# ezfet.net
KiCad netlist of a schematic drawn in Altium Designer
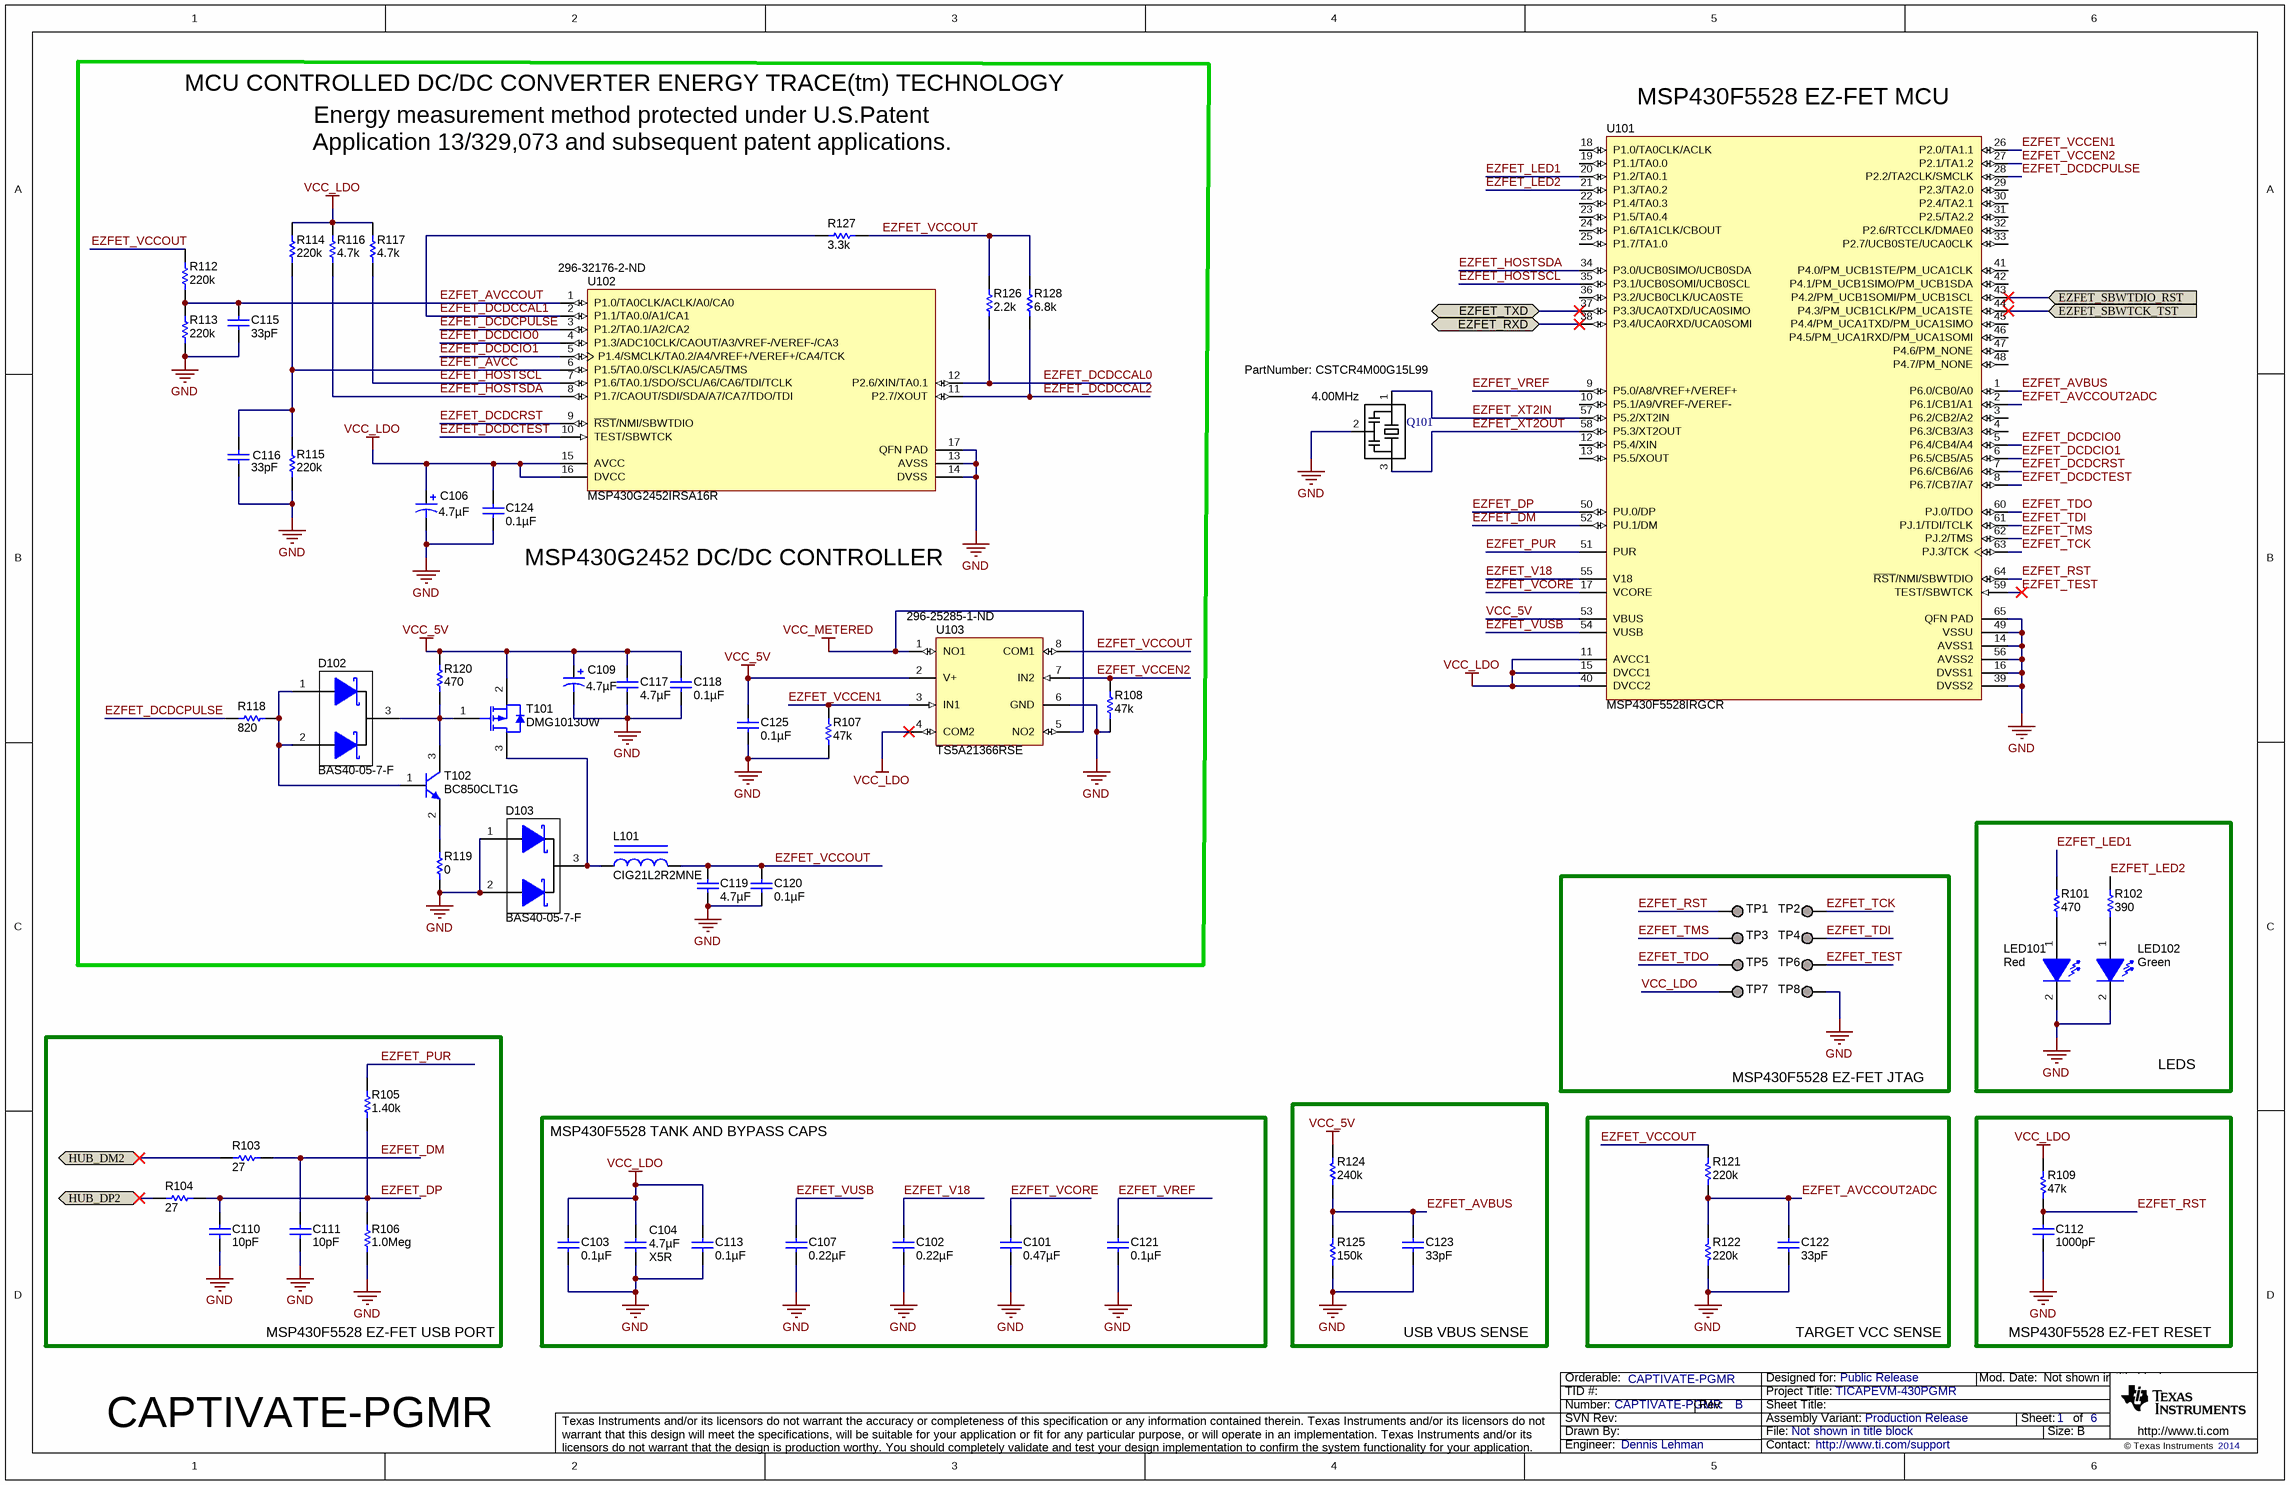
[diagram p0: ezfet.SchDoc]

(export (version "E")
  (design (tool "Eeschema 10.0.6"))
  (components
    (comp (ref "C101")
      (value "GRM155R61A474KE15D")
      (footprint "0402")
      (description "CAP, CERM, 0.47uF, 10V, +/-10%, X5R, 0402")
      (fields
        (field (name "VALUEDISPLAYED") "0.47µF")
        (field (name "MANUFACTURER") "MuRata")
        (field (name "PUBLISHER") "Texas Instruments")
      )
      (libsource (lib "Capacitor_Ceramic") (part "GRM155R61A474KE15D"))
    )
    (comp (ref "C102")
      (value "GRM155R61A224KE19D")
      (footprint "0402")
      (description "CAP, CERM, 0.22uF, 10V, +/-10%, X5R, 0402")
      (fields
        (field (name "VALUEDISPLAYED") "0.22µF")
        (field (name "MANUFACTURER") "MuRata")
        (field (name "PUBLISHER") "Texas Instruments")
      )
      (libsource (lib "Capacitor_Ceramic") (part "GRM155R61A224KE19D"))
    )
    (comp (ref "C103")
      (value "C1005X5R1A104K")
      (footprint "0402")
      (description "CAP, CERM, 0.1uF, 10V, +/-10%, X5R, 0402")
      (fields
        (field (name "VALUEDISPLAYED") "0.1µF")
        (field (name "MANUFACTURER") "TDK")
        (field (name "PUBLISHER") "Texas Instruments")
      )
      (libsource (lib "Capacitor_Ceramic") (part "C1005X5R1A104K"))
    )
    (comp (ref "C104")
      (value "CGB3B1X5R1A475K055AC")
      (footprint "0603")
      (description "CAP, CERM, 4.7 µF, 10 V, +/- 10%, X5R, 0603")
      (fields
        (field (name "VALUEDISPLAYED") "4.7µF")
        (field (name "MANUFACTURER") "TDK")
        (field (name "TEMPCO") "X5R")
        (field (name "PUBLISHER") "Texas Instruments")
      )
      (libsource (lib "Capacitor_Ceramic") (part "CGB3B1X5R1A475K055AC"))
    )
    (comp (ref "C106")
      (value "293D475X9010A2TE3")
      (footprint "3216-18")
      (description "CAP, TA, 4.7 µF, 10 V, +/- 10%, 5 ohm, SMD")
      (fields
        (field (name "VALUEDISPLAYED") "4.7µF")
        (field (name "MANUFACTURER") "Vishay-Sprague")
        (field (name "PUBLISHER") "Texas Instruments")
      )
      (libsource (lib "Capacitor_Tantalum") (part "293D475X9010A2TE3"))
    )
    (comp (ref "C107")
      (value "GRM155R61A224KE19D")
      (footprint "0402")
      (description "CAP, CERM, 0.22uF, 10V, +/-10%, X5R, 0402")
      (fields
        (field (name "VALUEDISPLAYED") "0.22µF")
        (field (name "MANUFACTURER") "MuRata")
        (field (name "PUBLISHER") "Texas Instruments")
      )
      (libsource (lib "Capacitor_Ceramic") (part "GRM155R61A224KE19D"))
    )
    (comp (ref "C109")
      (value "293D475X9010A2TE3")
      (footprint "3216-18")
      (description "CAP, TA, 4.7 µF, 10 V, +/- 10%, 5 ohm, SMD")
      (fields
        (field (name "VALUEDISPLAYED") "4.7µF")
        (field (name "MANUFACTURER") "Vishay-Sprague")
        (field (name "PUBLISHER") "Texas Instruments")
      )
      (libsource (lib "Capacitor_Tantalum") (part "293D475X9010A2TE3"))
    )
    (comp (ref "C110")
      (value "500R07S100JV4T")
      (footprint "0402")
      (description "CAP, CERM, 10pF, 50V, +/-5%, C0G/NP0, 0402")
      (fields
        (field (name "VALUEDISPLAYED") "10pF")
        (field (name "MANUFACTURER") "Johanson Technology")
        (field (name "PUBLISHER") "Texas Instruments")
      )
      (libsource (lib "Capacitor_Ceramic") (part "500R07S100JV4T"))
    )
    (comp (ref "C111")
      (value "500R07S100JV4T")
      (footprint "0402")
      (description "CAP, CERM, 10pF, 50V, +/-5%, C0G/NP0, 0402")
      (fields
        (field (name "VALUEDISPLAYED") "10pF")
        (field (name "MANUFACTURER") "Johanson Technology")
        (field (name "PUBLISHER") "Texas Instruments")
      )
      (libsource (lib "Capacitor_Ceramic") (part "500R07S100JV4T"))
    )
    (comp (ref "C112")
      (value "C1005X7R1H102K")
      (footprint "0402")
      (description "CAP, CERM, 1000pF, 50V, +/-10%, X7R, 0402")
      (fields
        (field (name "VALUEDISPLAYED") "1000pF")
        (field (name "MANUFACTURER") "TDK")
        (field (name "PUBLISHER") "Texas Instruments")
      )
      (libsource (lib "Capacitor_Ceramic") (part "C1005X7R1H102K"))
    )
    (comp (ref "C113")
      (value "C1005X5R1A104K")
      (footprint "0402")
      (description "CAP, CERM, 0.1uF, 10V, +/-10%, X5R, 0402")
      (fields
        (field (name "VALUEDISPLAYED") "0.1µF")
        (field (name "MANUFACTURER") "TDK")
        (field (name "PUBLISHER") "Texas Instruments")
      )
      (libsource (lib "Capacitor_Ceramic") (part "C1005X5R1A104K"))
    )
    (comp (ref "C115")
      (value "GRM1555C1H330JA01D")
      (footprint "0402")
      (description "CAP, CERM, 33pF, 50V, +/-5%, C0G/NP0, 0402")
      (fields
        (field (name "VALUEDISPLAYED") "33pF")
        (field (name "MANUFACTURER") "MuRata")
        (field (name "PUBLISHER") "Texas Instruments")
      )
      (libsource (lib "Capacitor_Ceramic") (part "GRM1555C1H330JA01D"))
    )
    (comp (ref "C116")
      (value "GRM1555C1H330JA01D")
      (footprint "0402")
      (description "CAP, CERM, 33pF, 50V, +/-5%, C0G/NP0, 0402")
      (fields
        (field (name "VALUEDISPLAYED") "33pF")
        (field (name "MANUFACTURER") "MuRata")
        (field (name "PUBLISHER") "Texas Instruments")
      )
      (libsource (lib "Capacitor_Ceramic") (part "GRM1555C1H330JA01D"))
    )
    (comp (ref "C117")
      (value "0603ZD475KAT2A")
      (footprint "0603")
      (description "CAP, CERM, 4.7 µF, 10 V, +/- 10%, X5R, 0603")
      (fields
        (field (name "VALUEDISPLAYED") "4.7µF")
        (field (name "MANUFACTURER") "AVX")
        (field (name "PUBLISHER") "Texas Instruments")
      )
      (libsource (lib "Capacitor_Ceramic") (part "0603ZD475KAT2A"))
    )
    (comp (ref "C118")
      (value "C1005X5R1A104K")
      (footprint "0402")
      (description "CAP, CERM, 0.1uF, 10V, +/-10%, X5R, 0402")
      (fields
        (field (name "VALUEDISPLAYED") "0.1µF")
        (field (name "MANUFACTURER") "TDK")
        (field (name "PUBLISHER") "Texas Instruments")
      )
      (libsource (lib "Capacitor_Ceramic") (part "C1005X5R1A104K"))
    )
    (comp (ref "C119")
      (value "0603ZD475KAT2A")
      (footprint "0603")
      (description "CAP, CERM, 4.7 µF, 10 V, +/- 10%, X5R, 0603")
      (fields
        (field (name "VALUEDISPLAYED") "4.7µF")
        (field (name "MANUFACTURER") "AVX")
        (field (name "PUBLISHER") "Texas Instruments")
      )
      (libsource (lib "Capacitor_Ceramic") (part "0603ZD475KAT2A"))
    )
    (comp (ref "C120")
      (value "C1005X5R1A104K")
      (footprint "0402")
      (description "CAP, CERM, 0.1uF, 10V, +/-10%, X5R, 0402")
      (fields
        (field (name "VALUEDISPLAYED") "0.1µF")
        (field (name "MANUFACTURER") "TDK")
        (field (name "PUBLISHER") "Texas Instruments")
      )
      (libsource (lib "Capacitor_Ceramic") (part "C1005X5R1A104K"))
    )
    (comp (ref "C121")
      (value "C1005X5R1A104K")
      (footprint "0402")
      (description "CAP, CERM, 0.1uF, 10V, +/-10%, X5R, 0402")
      (fields
        (field (name "VALUEDISPLAYED") "0.1µF")
        (field (name "MANUFACTURER") "TDK")
        (field (name "PUBLISHER") "Texas Instruments")
      )
      (libsource (lib "Capacitor_Ceramic") (part "C1005X5R1A104K"))
    )
    (comp (ref "C122")
      (value "GRM1555C1H330JA01D")
      (footprint "0402")
      (description "CAP, CERM, 33pF, 50V, +/-5%, C0G/NP0, 0402")
      (fields
        (field (name "VALUEDISPLAYED") "33pF")
        (field (name "MANUFACTURER") "MuRata")
        (field (name "PUBLISHER") "Texas Instruments")
      )
      (libsource (lib "Capacitor_Ceramic") (part "GRM1555C1H330JA01D"))
    )
    (comp (ref "C123")
      (value "GRM1555C1H330JA01D")
      (footprint "0402")
      (description "CAP, CERM, 33pF, 50V, +/-5%, C0G/NP0, 0402")
      (fields
        (field (name "VALUEDISPLAYED") "33pF")
        (field (name "MANUFACTURER") "MuRata")
        (field (name "PUBLISHER") "Texas Instruments")
      )
      (libsource (lib "Capacitor_Ceramic") (part "GRM1555C1H330JA01D"))
    )
    (comp (ref "C124")
      (value "C1005X5R1A104K")
      (footprint "0402")
      (description "CAP, CERM, 0.1 µF, 10 V, +/- 10%, X5R, 0402")
      (fields
        (field (name "VALUEDISPLAYED") "0.1µF")
        (field (name "MANUFACTURER") "TDK")
        (field (name "PUBLISHER") "Texas Instruments")
      )
      (libsource (lib "Capacitor_Ceramic") (part "C1005X5R1A104K"))
    )
    (comp (ref "C125")
      (value "C1005X5R1A104K")
      (footprint "0402")
      (description "CAP, CERM, 0.1uF, 10V, +/-10%, X5R, 0402")
      (fields
        (field (name "VALUEDISPLAYED") "0.1µF")
        (field (name "MANUFACTURER") "TDK")
        (field (name "PUBLISHER") "Texas Instruments")
      )
      (libsource (lib "Capacitor_Ceramic") (part "C1005X5R1A104K"))
    )
    (comp (ref "D102")
      (value "BAS40-05-7-F")
      (footprint "SOT-23")
      (description "Diode, Schottky, 40V, 0.2A, SOT-23")
      (fields
        (field (name "MANUFACTURER") "Diodes Inc.")
        (field (name "SYMBOLCREATOR") "a0412235")
        (field (name "PUBLISHER") "Texas Instruments")
      )
      (libsource (lib "Diode") (part "BAS40-05-7-F"))
    )
    (comp (ref "D103")
      (value "BAS40-05-7-F")
      (footprint "SOT-23")
      (description "Diode, Schottky, 40V, 0.2A, SOT-23")
      (fields
        (field (name "MANUFACTURER") "Diodes Inc.")
        (field (name "SYMBOLCREATOR") "a0412235")
        (field (name "PUBLISHER") "Texas Instruments")
      )
      (libsource (lib "Diode") (part "BAS40-05-7-F"))
    )
    (comp (ref "L101")
      (value "CIG21L2R2MNE")
      (footprint "0805_HV")
      (description "Inductor, Shielded, Composite, 2.2uH, 0.95A, 0.16 ohm, SMD")
      (fields (field (name "MANUFACTURER") "Samsung") (field (name "PUBLISHER") "Texas Instruments"))
      (libsource (lib "Inductor_Other") (part "CIG21L2R2MNE"))
    )
    (comp (ref "LED101")
      (value "Red")
      (footprint "LED_LTST-C190_Red")
      (description "LED, Red, SMD")
      (fields
        (field (name "MANUFACTURER") "Lite-On")
        (field (name "PARTNUMBER") "LTST-C190CKT")
        (field (name "PUBLISHER") "Texas Instruments")
      )
      (libsource (lib "LED") (part "LTST-C190CKT"))
    )
    (comp (ref "LED102")
      (value "Green")
      (footprint "LED_LTST-C190")
      (description "LED, Green, SMD")
      (fields
        (field (name "MANUFACTURER") "Lite-On")
        (field (name "PARTNUMBER") "LTST-C190GKT")
        (field (name "PUBLISHER") "Texas Instruments")
      )
      (libsource (lib "LED") (part "LTST-C190GKT"))
    )
    (comp (ref "Q101")
      (value "MURATA-FILTER_CSTCR4M00G15")
      (footprint "CSTCR CERAMIC RESONATOR - MURATA")
      (description "4.00MHz resonator")
      (fields (field (name "VALUE DISPLAYED") "4.00MHz") (field (name "PARTNUMBER") "CSTCR4M00G15L99"))
      (libsource (lib "Captivate Library") (part "MURATA-FILTER_CSTCR4M00G15"))
    )
    (comp (ref "R101")
      (value "470")
      (footprint "0402")
      (description "RES, 470 ohm, 5%, 0.063W, 0402")
      (fields
        (field (name "PARTNUMBER") "CRCW0402470RJNED")
        (field (name "MANUFACTURER") "Vishay-Dale")
        (field (name "PUBLISHER") "Texas Instruments")
      )
      (libsource (lib "Resistor_0402") (part "CRCW0402470RJNED"))
    )
    (comp (ref "R102")
      (value "390")
      (footprint "0402")
      (description "RES, 390 ohm, 5%, 0.063W, 0402")
      (fields
        (field (name "PARTNUMBER") "CRCW0402390RJNED")
        (field (name "MANUFACTURER") "Vishay-Dale")
        (field (name "PUBLISHER") "Texas Instruments")
      )
      (libsource (lib "Resistor_0402") (part "CRCW0402390RJNED"))
    )
    (comp (ref "R103")
      (value "27")
      (footprint "0402")
      (description "RES, 27 ohm, 5%, 0.063W, 0402")
      (fields
        (field (name "PARTNUMBER") "CRCW040227R0JNED")
        (field (name "MANUFACTURER") "Vishay-Dale")
        (field (name "PUBLISHER") "Texas Instruments")
      )
      (libsource (lib "Resistor_0402") (part "CRCW040227R0JNED"))
    )
    (comp (ref "R104")
      (value "27")
      (footprint "0402")
      (description "RES, 27 ohm, 5%, 0.063W, 0402")
      (fields
        (field (name "PARTNUMBER") "CRCW040227R0JNED")
        (field (name "MANUFACTURER") "Vishay-Dale")
        (field (name "PUBLISHER") "Texas Instruments")
      )
      (libsource (lib "Resistor_0402") (part "CRCW040227R0JNED"))
    )
    (comp (ref "R105")
      (value "CRCW04021K40FKED")
      (footprint "0402")
      (description "RES, 1.40 k, 1%, 0.063 W, 0402")
      (fields
        (field (name "MANUFACTURER") "Vishay-Dale")
        (field (name "VALUEDISPLAYED") "1.40k")
        (field (name "PUBLISHER") "Texas Instruments")
      )
      (libsource (lib "Resistor_0402") (part "CRCW04021K40FKED"))
    )
    (comp (ref "R106")
      (value "1.0Meg")
      (footprint "0402")
      (description "RES, 1.0Meg ohm, 5%, 0.063W, 0402")
      (fields
        (field (name "PARTNUMBER") "CRCW04021M00JNED")
        (field (name "MANUFACTURER") "Vishay-Dale")
        (field (name "PUBLISHER") "Texas Instruments")
      )
      (libsource (lib "Resistor_0402") (part "CRCW04021M00JNED"))
    )
    (comp (ref "R107")
      (value "CRCW040247K0JNED")
      (footprint "0402")
      (description "RES, 47 k, 5%, 0.063 W, 0402")
      (fields
        (field (name "MANUFACTURER") "Vishay-Dale")
        (field (name "VALUEDISPLAYED") "47k")
        (field (name "PUBLISHER") "Texas Instruments")
      )
      (libsource (lib "Resistor_0402") (part "CRCW040247K0JNED"))
    )
    (comp (ref "R108")
      (value "CRCW040247K0JNED")
      (footprint "0402")
      (description "RES, 47 k, 5%, 0.063 W, 0402")
      (fields
        (field (name "MANUFACTURER") "Vishay-Dale")
        (field (name "VALUEDISPLAYED") "47k")
        (field (name "PUBLISHER") "Texas Instruments")
      )
      (libsource (lib "Resistor_0402") (part "CRCW040247K0JNED"))
    )
    (comp (ref "R109")
      (value "47k")
      (footprint "0402")
      (description "RES, 47k ohm, 5%, 0.063W, 0402")
      (fields
        (field (name "PARTNUMBER") "CRCW040247K0JNED")
        (field (name "MANUFACTURER") "Vishay-Dale")
        (field (name "PUBLISHER") "Texas Instruments")
      )
      (libsource (lib "Resistor_0402") (part "CRCW040247K0JNED"))
    )
    (comp (ref "R112")
      (value "CRCW0402220KJNED")
      (footprint "0402")
      (description "RES, 220 k, 5%, 0.063 W, 0402")
      (fields
        (field (name "VALUEDISPLAYED") "220k")
        (field (name "MANUFACTURER") "Vishay-Dale")
        (field (name "PUBLISHER") "Texas Instruments")
      )
      (libsource (lib "Resistor_0402") (part "CRCW0402220KJNED"))
    )
    (comp (ref "R113")
      (value "CRCW0402220KJNED")
      (footprint "0402")
      (description "RES, 220 k, 5%, 0.063 W, 0402")
      (fields
        (field (name "VALUEDISPLAYED") "220k")
        (field (name "MANUFACTURER") "Vishay-Dale")
        (field (name "PUBLISHER") "Texas Instruments")
      )
      (libsource (lib "Resistor_0402") (part "CRCW0402220KJNED"))
    )
    (comp (ref "R114")
      (value "CRCW0402220KJNED")
      (footprint "0402")
      (description "RES, 220 k, 5%, 0.063 W, 0402")
      (fields
        (field (name "VALUEDISPLAYED") "220k")
        (field (name "MANUFACTURER") "Vishay-Dale")
        (field (name "PUBLISHER") "Texas Instruments")
      )
      (libsource (lib "Resistor_0402") (part "CRCW0402220KJNED"))
    )
    (comp (ref "R115")
      (value "CRCW0402220KJNED")
      (footprint "0402")
      (description "RES, 220 k, 5%, 0.063 W, 0402")
      (fields
        (field (name "VALUEDISPLAYED") "220k")
        (field (name "MANUFACTURER") "Vishay-Dale")
        (field (name "PUBLISHER") "Texas Instruments")
      )
      (libsource (lib "Resistor_0402") (part "CRCW0402220KJNED"))
    )
    (comp (ref "R116")
      (value "CRCW04024K70JNED")
      (footprint "0402")
      (description "RES, 4.7 k, 5%, 0.063 W, 0402")
      (fields
        (field (name "VALUEDISPLAYED") "4.7k")
        (field (name "MANUFACTURER") "Vishay-Dale")
        (field (name "PUBLISHER") "Texas Instruments")
      )
      (libsource (lib "Resistor_0402") (part "CRCW04024K70JNED"))
    )
    (comp (ref "R117")
      (value "CRCW04024K70JNED")
      (footprint "0402")
      (description "RES, 4.7 k, 5%, 0.063 W, 0402")
      (fields
        (field (name "VALUEDISPLAYED") "4.7k")
        (field (name "MANUFACTURER") "Vishay-Dale")
        (field (name "PUBLISHER") "Texas Instruments")
      )
      (libsource (lib "Resistor_0402") (part "CRCW04024K70JNED"))
    )
    (comp (ref "R118")
      (value "CRCW0402820RJNED")
      (footprint "0402")
      (description "RES, 820, 5%, 0.063 W, 0402")
      (fields
        (field (name "MANUFACTURER") "Vishay-Dale")
        (field (name "VALUEDISPLAYED") "820")
        (field (name "PUBLISHER") "Texas Instruments")
      )
      (libsource (lib "Resistor_0402") (part "CRCW0402820RJNED"))
    )
    (comp (ref "R119")
      (value "CRCW04020000Z0ED")
      (footprint "0402")
      (description "RES, 0, 5%, 0.063 W, 0402")
      (fields
        (field (name "MANUFACTURER") "Vishay-Dale")
        (field (name "VALUEDISPLAYED") "0")
        (field (name "PUBLISHER") "Texas Instruments")
      )
      (libsource (lib "Resistor_0402") (part "CRCW04020000Z0ED"))
    )
    (comp (ref "R120")
      (value "CRCW0402470RJNED")
      (footprint "0402")
      (description "RES, 470, 5%, 0.063 W, 0402")
      (fields
        (field (name "MANUFACTURER") "Vishay-Dale")
        (field (name "VALUEDISPLAYED") "470")
        (field (name "PUBLISHER") "Texas Instruments")
      )
      (libsource (lib "Resistor_0402") (part "CRCW0402470RJNED"))
    )
    (comp (ref "R121")
      (value "220k")
      (footprint "0402")
      (description "RES, 220k ohm, 5%, 0.063W, 0402")
      (fields
        (field (name "PARTNUMBER") "CRCW0402220KJNED")
        (field (name "MANUFACTURER") "Vishay-Dale")
        (field (name "PUBLISHER") "Texas Instruments")
      )
      (libsource (lib "Resistor_0402") (part "CRCW0402220KJNED"))
    )
    (comp (ref "R122")
      (value "220k")
      (footprint "0402")
      (description "RES, 220k ohm, 5%, 0.063W, 0402")
      (fields
        (field (name "PARTNUMBER") "CRCW0402220KJNED")
        (field (name "MANUFACTURER") "Vishay-Dale")
        (field (name "PUBLISHER") "Texas Instruments")
      )
      (libsource (lib "Resistor_0402") (part "CRCW0402220KJNED"))
    )
    (comp (ref "R124")
      (value "240k")
      (footprint "0402")
      (description "RES, 240k ohm, 5%, 0.063W, 0402")
      (fields
        (field (name "PARTNUMBER") "CRCW0402240KJNED")
        (field (name "MANUFACTURER") "Vishay-Dale")
        (field (name "PUBLISHER") "Texas Instruments")
      )
      (libsource (lib "Resistor_0402") (part "CRCW0402240KJNED"))
    )
    (comp (ref "R125")
      (value "150k")
      (footprint "0402")
      (description "RES, 150k ohm, 1%, 0.063W, 0402")
      (fields
        (field (name "PARTNUMBER") "CRCW0402150KFKED")
        (field (name "MANUFACTURER") "Vishay-Dale")
        (field (name "PUBLISHER") "Texas Instruments")
      )
      (libsource (lib "Resistor_0402") (part "CRCW0402150KFKED"))
    )
    (comp (ref "R126")
      (value "CRCW04022K20JNED")
      (footprint "0402")
      (description "RES, 2.2 k, 5%, 0.063 W, 0402")
      (fields
        (field (name "VALUEDISPLAYED") "2.2k")
        (field (name "MANUFACTURER") "Vishay-Dale")
        (field (name "PUBLISHER") "Texas Instruments")
      )
      (libsource (lib "Resistor_0402") (part "CRCW04022K20JNED"))
    )
    (comp (ref "R127")
      (value "CRCW04023K30JNED")
      (footprint "0402")
      (description "RES, 3.3 k, 5%, 0.063 W, 0402")
      (fields
        (field (name "VALUEDISPLAYED") "3.3k")
        (field (name "MANUFACTURER") "Vishay-Dale")
        (field (name "PUBLISHER") "Texas Instruments")
      )
      (libsource (lib "Resistor_0402") (part "CRCW04023K30JNED"))
    )
    (comp (ref "R128")
      (value "CRCW04026K80JNED")
      (footprint "0402")
      (description "RES, 6.8 k, 5%, 0.063 W, 0402")
      (fields
        (field (name "VALUEDISPLAYED") "6.8k")
        (field (name "MANUFACTURER") "Vishay-Dale")
        (field (name "PUBLISHER") "Texas Instruments")
      )
      (libsource (lib "Resistor_0402") (part "CRCW04026K80JNED"))
    )
    (comp (ref "T101")
      (value "DMG1013UW")
      (footprint "SOT-323")
      (description "MOSFET, P-CH, -50V, -0.13A, SOT-323")
      (fields
        (field (name "PARTNUMBER") "BSS84W-7-F")
        (field (name "MANUFACTURER") "Diodes Inc.")
        (field (name "PUBLISHER") "Texas Instruments")
      )
      (libsource (lib "FETs") (part "BSS84W-7-F"))
    )
    (comp (ref "T102")
      (value "BC850CLT1G")
      (footprint "SOT-23")
      (description "Transistor, NPN, 45V, 0.1A, SOT-23")
      (fields (field (name "MANUFACTURER") "ON Semiconductor") (field (name "PUBLISHER") "Texas Instruments"))
      (libsource (lib "Bipolar_Transistor") (part "BC850CLT1G, ON Semiconductor"))
    )
    (comp (ref "TP1")
      (value "TESTPOINT")
      (footprint "TP_VIA_060RND040")
      (description "TEST POINT.  No entry in BOM.")
      (fields (field (name "PUBLISHER") "Texas Instruments"))
      (libsource (lib "MiscParts") (part "TESTPOINT"))
    )
    (comp (ref "TP2")
      (value "TESTPOINT")
      (footprint "TP_VIA_060RND040")
      (description "TEST POINT.  No entry in BOM.")
      (fields (field (name "PUBLISHER") "Texas Instruments"))
      (libsource (lib "MiscParts") (part "TESTPOINT"))
    )
    (comp (ref "TP3")
      (value "TESTPOINT")
      (footprint "TP_VIA_060RND040")
      (description "TEST POINT.  No entry in BOM.")
      (fields (field (name "PUBLISHER") "Texas Instruments"))
      (libsource (lib "MiscParts") (part "TESTPOINT"))
    )
    (comp (ref "TP4")
      (value "TESTPOINT")
      (footprint "TP_VIA_060RND040")
      (description "TEST POINT.  No entry in BOM.")
      (fields (field (name "PUBLISHER") "Texas Instruments"))
      (libsource (lib "MiscParts") (part "TESTPOINT"))
    )
    (comp (ref "TP5")
      (value "TESTPOINT")
      (footprint "TP_VIA_060RND040")
      (description "TEST POINT.  No entry in BOM.")
      (fields (field (name "PUBLISHER") "Texas Instruments"))
      (libsource (lib "MiscParts") (part "TESTPOINT"))
    )
    (comp (ref "TP6")
      (value "TESTPOINT")
      (footprint "TP_VIA_060RND040")
      (description "TEST POINT.  No entry in BOM.")
      (fields (field (name "PUBLISHER") "Texas Instruments"))
      (libsource (lib "MiscParts") (part "TESTPOINT"))
    )
    (comp (ref "TP7")
      (value "TESTPOINT")
      (footprint "TP_VIA_060RND040")
      (description "TEST POINT.  No entry in BOM.")
      (fields (field (name "PUBLISHER") "Texas Instruments"))
      (libsource (lib "MiscParts") (part "TESTPOINT"))
    )
    (comp (ref "TP8")
      (value "TESTPOINT")
      (footprint "TP_VIA_060RND040")
      (description "TEST POINT.  No entry in BOM.")
      (fields (field (name "PUBLISHER") "Texas Instruments"))
      (libsource (lib "MiscParts") (part "TESTPOINT"))
    )
    (comp (ref "U101")
      (value "MSP430F5528IRGCR")
      (footprint "RGC0064B")
      (fields (field (name "MANUFACTURER") "Texas Instruments"))
      (libsource (lib "TI MCU MSP430") (part "MSP430F5528IRGCR"))
    )
    (comp (ref "U102")
      (value "MSP430G2452IRSA16R")
      (footprint "RSA0016B:RSA0016B")
      (fields
        (field (name "ALTERNATE PARTNUMBER") "Equivalent")
        (field (name "MANUFACTURER") "Texas Instruments")
        (field (name "SUPPLIER PART NUMBER 1") "296-32176-2-ND")
      )
      (libsource (lib "TI MCU MSP430") (part "MSP430G2452IRSA16R"))
    )
    (comp (ref "U103")
      (value "TS5A21366RSE")
      (footprint "RSE0008A")
      (description "0.75-Ω DUAL SPST ANALOG SWITCH WITH 1.8-V COMPATIBLE INPUT LOGIC, RSE0008A")
      (fields
        (field (name "MANUFACTURER") "Texas Instruments")
        (field (name "SUPPLIER PART NUMBER 1") "296-25285-1-ND")
        (field (name "SYMBOLCREATOR") "a0272918")
        (field (name "PUBLISHER") "Texas Instruments")
      )
      (libsource (lib "Captivate Library") (part "TS5A21366RSE"))
    )
  )
  (nets
    (net (code "1") (name "/EZFET_AVBUS") (class "Default")
      (node (ref "C123") (pin "1") (pinfunction "1_1") (pintype "passive"))
      (node (ref "R124") (pin "1") (pinfunction "1_1") (pintype "passive"))
      (node (ref "R125") (pin "2") (pinfunction "2_2") (pintype "passive"))
      (node (ref "U101") (pin "1") (pinfunction "P6.0/CB0/A0_1") (pintype "bidirectional"))
    )
    (net (code "2") (name "/EZFET_AVCC") (class "Default")
      (node (ref "C116") (pin "1") (pinfunction "1_1") (pintype "passive"))
      (node (ref "R114") (pin "1") (pinfunction "1_1") (pintype "passive"))
      (node (ref "R115") (pin "2") (pinfunction "2_2") (pintype "passive"))
      (node (ref "U102") (pin "6") (pinfunction "P1.5/TA0.0/SCLK/A5/CA5/TMS_6") (pintype "bidirectional"))
    )
    (net (code "3") (name "/EZFET_AVCCOUT") (class "Default")
      (node (ref "C115") (pin "1") (pinfunction "1_1") (pintype "passive"))
      (node (ref "R112") (pin "1") (pinfunction "1_1") (pintype "passive"))
      (node (ref "R113") (pin "2") (pinfunction "2_2") (pintype "passive"))
      (node (ref "U102") (pin "1") (pinfunction "P1.0/TA0CLK/ACLK/A0/CA0_1") (pintype "bidirectional"))
    )
    (net (code "4") (name "/EZFET_AVCCOUT2ADC") (class "Default")
      (node (ref "C122") (pin "1") (pinfunction "1_1") (pintype "passive"))
      (node (ref "R121") (pin "1") (pinfunction "1_1") (pintype "passive"))
      (node (ref "R122") (pin "2") (pinfunction "2_2") (pintype "passive"))
      (node (ref "U101") (pin "2") (pinfunction "P6.1/CB1/A1_2") (pintype "bidirectional"))
    )
    (net (code "5") (name "/EZFET_DCDCCAL0") (class "Default")
      (node (ref "R126") (pin "1") (pinfunction "1_1") (pintype "passive"))
      (node (ref "U102") (pin "12") (pinfunction "P2.6/XIN/TA0.1_12") (pintype "bidirectional"))
    )
    (net (code "6") (name "/EZFET_DCDCCAL1") (class "Default")
      (node (ref "R127") (pin "1") (pinfunction "1_1") (pintype "passive"))
      (node (ref "U102") (pin "2") (pinfunction "P1.1/TA0.0/A1/CA1_2") (pintype "bidirectional"))
    )
    (net (code "7") (name "/EZFET_DCDCCAL2") (class "Default")
      (node (ref "R128") (pin "1") (pinfunction "1_1") (pintype "passive"))
      (node (ref "U102") (pin "11") (pinfunction "P2.7/XOUT_11") (pintype "bidirectional"))
    )
    (net (code "8") (name "/EZFET_DCDCIO0") (class "Default")
      (node (ref "U101") (pin "5") (pinfunction "P6.4/CB4/A4_5") (pintype "bidirectional"))
      (node (ref "U102") (pin "4") (pinfunction "P1.3/ADC10CLK/CAOUT/A3/VREF-/VEREF-/CA3_4") (pintype "bidirectional"))
    )
    (net (code "9") (name "/EZFET_DCDCIO1") (class "Default")
      (node (ref "U101") (pin "6") (pinfunction "P6.5/CB5/A5_6") (pintype "bidirectional"))
      (node (ref "U102") (pin "5") (pinfunction "P1.4/SMCLK/TA0.2/A4/VREF+/VEREF+/CA4/TCK_5") (pintype "bidirectional"))
    )
    (net (code "10") (name "/EZFET_DCDCPULSE") (class "Default")
      (node (ref "R118") (pin "2") (pinfunction "2_2") (pintype "passive"))
      (node (ref "U101") (pin "28") (pinfunction "P2.2/TA2CLK/SMCLK_28") (pintype "bidirectional"))
      (node (ref "U102") (pin "3") (pinfunction "P1.2/TA0.1/A2/CA2_3") (pintype "bidirectional"))
    )
    (net (code "11") (name "/EZFET_DCDCRST") (class "Default")
      (node (ref "U101") (pin "7") (pinfunction "P6.6/CB6/A6_7") (pintype "bidirectional"))
      (node (ref "U102") (pin "9") (pinfunction "~{RST}/NMI/SBWTDIO_9") (pintype "bidirectional"))
    )
    (net (code "12") (name "/EZFET_DCDCTEST") (class "Default")
      (node (ref "U101") (pin "8") (pinfunction "P6.7/CB7/A7_8") (pintype "bidirectional"))
      (node (ref "U102") (pin "10") (pinfunction "TEST/SBWTCK_10") (pintype "input"))
    )
    (net (code "13") (name "/EZFET_DM") (class "Default")
      (node (ref "C111") (pin "1") (pinfunction "1_1") (pintype "passive"))
      (node (ref "R103") (pin "2") (pinfunction "2_2") (pintype "passive"))
      (node (ref "U101") (pin "52") (pinfunction "PU.1/DM_52") (pintype "bidirectional"))
    )
    (net (code "14") (name "/EZFET_DP") (class "Default")
      (node (ref "C110") (pin "1") (pinfunction "1_1") (pintype "passive"))
      (node (ref "R104") (pin "2") (pinfunction "2_2") (pintype "passive"))
      (node (ref "R105") (pin "2") (pinfunction "2_2") (pintype "passive"))
      (node (ref "R106") (pin "1") (pinfunction "1_1") (pintype "passive"))
      (node (ref "U101") (pin "50") (pinfunction "PU.0/DP_50") (pintype "bidirectional"))
    )
    (net (code "15") (name "/EZFET_HOSTSCL") (class "Default")
      (node (ref "R117") (pin "1") (pinfunction "1_1") (pintype "passive"))
      (node (ref "U101") (pin "35") (pinfunction "P3.1/UCB0SOMI/UCB0SCL_35") (pintype "bidirectional"))
      (node (ref "U102") (pin "7") (pinfunction "P1.6/TA0.1/SDO/SCL/A6/CA6/TDI/TCLK_7") (pintype "bidirectional"))
    )
    (net (code "16") (name "/EZFET_HOSTSDA") (class "Default")
      (node (ref "R116") (pin "1") (pinfunction "1_1") (pintype "passive"))
      (node (ref "U101") (pin "34") (pinfunction "P3.0/UCB0SIMO/UCB0SDA_34") (pintype "bidirectional"))
      (node (ref "U102") (pin "8") (pinfunction "P1.7/CAOUT/SDI/SDA/A7/CA7/TDO/TDI_8") (pintype "bidirectional"))
    )
    (net (code "17") (name "/EZFET_LED1") (class "Default")
      (node (ref "R101") (pin "2") (pinfunction "2_2") (pintype "passive"))
      (node (ref "U101") (pin "20") (pinfunction "P1.2/TA0.1_20") (pintype "bidirectional"))
    )
    (net (code "18") (name "/EZFET_LED2") (class "Default")
      (node (ref "R102") (pin "2") (pinfunction "2_2") (pintype "passive"))
      (node (ref "U101") (pin "21") (pinfunction "P1.3/TA0.2_21") (pintype "bidirectional"))
    )
    (net (code "19") (name "/EZFET_PUR") (class "Default")
      (node (ref "R105") (pin "1") (pinfunction "1_1") (pintype "passive"))
      (node (ref "U101") (pin "51") (pinfunction "PUR_51") (pintype "passive"))
    )
    (net (code "20") (name "/EZFET_RST") (class "Default")
      (node (ref "C112") (pin "1") (pinfunction "1_1") (pintype "passive"))
      (node (ref "R109") (pin "1") (pinfunction "1_1") (pintype "passive"))
      (node (ref "TP1") (pin "1") (pintype "passive"))
      (node (ref "U101") (pin "64") (pinfunction "~{RST}/NMI/SBWTDIO_64") (pintype "bidirectional"))
    )
    (net (code "21") (name "/EZFET_RXD") (class "Default")
      (node (ref "U101") (pin "38") (pinfunction "P3.4/UCA0RXD/UCA0SOMI_38") (pintype "bidirectional+no_connect"))
    )
    (net (code "22") (name "/EZFET_SBWTCK_TST") (class "Default")
      (node (ref "U101") (pin "44") (pinfunction "P4.3/PM_UCB1CLK/PM_UCA1STE_44") (pintype "bidirectional+no_connect"))
    )
    (net (code "23") (name "/EZFET_SBWTDIO_RST") (class "Default")
      (node (ref "U101") (pin "43") (pinfunction "P4.2/PM_UCB1SOMI/PM_UCB1SCL_43") (pintype "bidirectional+no_connect"))
    )
    (net (code "24") (name "/EZFET_TCK") (class "Default")
      (node (ref "TP2") (pin "1") (pintype "passive"))
      (node (ref "U101") (pin "63") (pinfunction "PJ.3/TCK_63") (pintype "bidirectional"))
    )
    (net (code "25") (name "/EZFET_TDI") (class "Default")
      (node (ref "TP4") (pin "1") (pintype "passive"))
      (node (ref "U101") (pin "61") (pinfunction "PJ.1/TDI/TCLK_61") (pintype "bidirectional"))
    )
    (net (code "26") (name "/EZFET_TDO") (class "Default")
      (node (ref "TP5") (pin "1") (pintype "passive"))
      (node (ref "U101") (pin "60") (pinfunction "PJ.0/TDO_60") (pintype "bidirectional"))
    )
    (net (code "27") (name "/EZFET_TEST") (class "Default")
      (node (ref "TP6") (pin "1") (pintype "passive"))
      (node (ref "U101") (pin "59") (pinfunction "TEST/SBWTCK_59") (pintype "input"))
    )
    (net (code "28") (name "/EZFET_TMS") (class "Default")
      (node (ref "TP3") (pin "1") (pintype "passive"))
      (node (ref "U101") (pin "62") (pinfunction "PJ.2/TMS_62") (pintype "bidirectional"))
    )
    (net (code "29") (name "/EZFET_TXD") (class "Default")
      (node (ref "U101") (pin "37") (pinfunction "P3.3/UCA0TXD/UCA0SIMO_37") (pintype "bidirectional+no_connect"))
    )
    (net (code "30") (name "/EZFET_V18") (class "Default")
      (node (ref "C102") (pin "1") (pinfunction "1_1") (pintype "passive"))
      (node (ref "U101") (pin "55") (pinfunction "V18_55") (pintype "passive"))
    )
    (net (code "31") (name "/EZFET_VCCEN1") (class "Default")
      (node (ref "R107") (pin "2") (pinfunction "2_2") (pintype "passive"))
      (node (ref "U101") (pin "26") (pinfunction "P2.0/TA1.1_26") (pintype "bidirectional"))
      (node (ref "U103") (pin "3") (pinfunction "IN1_3") (pintype "input"))
    )
    (net (code "32") (name "/EZFET_VCCEN2") (class "Default")
      (node (ref "R108") (pin "2") (pinfunction "2_2") (pintype "passive"))
      (node (ref "U101") (pin "27") (pinfunction "P2.1/TA1.2_27") (pintype "bidirectional"))
      (node (ref "U103") (pin "7") (pinfunction "IN2_7") (pintype "input"))
    )
    (net (code "33") (name "/EZFET_VCCOUT") (class "Default")
      (node (ref "C119") (pin "1") (pinfunction "1_1") (pintype "passive"))
      (node (ref "C120") (pin "1") (pinfunction "1_1") (pintype "passive"))
      (node (ref "L101") (pin "2") (pinfunction "2_2") (pintype "passive"))
      (node (ref "R112") (pin "2") (pinfunction "2_2") (pintype "passive"))
      (node (ref "R121") (pin "2") (pinfunction "2_2") (pintype "passive"))
      (node (ref "R126") (pin "2") (pinfunction "2_2") (pintype "passive"))
      (node (ref "R127") (pin "2") (pinfunction "2_2") (pintype "passive"))
      (node (ref "R128") (pin "2") (pinfunction "2_2") (pintype "passive"))
      (node (ref "U103") (pin "8") (pinfunction "COM1_8") (pintype "bidirectional"))
    )
    (net (code "34") (name "/EZFET_VCORE") (class "Default")
      (node (ref "C101") (pin "1") (pinfunction "1_1") (pintype "passive"))
      (node (ref "U101") (pin "17") (pinfunction "VCORE_17") (pintype "passive"))
    )
    (net (code "35") (name "/EZFET_VREF") (class "Default")
      (node (ref "C121") (pin "1") (pinfunction "1_1") (pintype "passive"))
      (node (ref "U101") (pin "9") (pinfunction "P5.0/A8/VREF+/VEREF+_9") (pintype "bidirectional"))
    )
    (net (code "36") (name "/EZFET_VUSB") (class "Default")
      (node (ref "C107") (pin "1") (pinfunction "1_1") (pintype "passive"))
      (node (ref "U101") (pin "54") (pinfunction "VUSB_54") (pintype "power_in"))
    )
    (net (code "37") (name "/EZFET_XT2IN") (class "Default")
      (node (ref "Q101") (pin "1") (pinfunction "1_1") (pintype "passive"))
      (node (ref "U101") (pin "57") (pinfunction "P5.2/XT2IN_57") (pintype "bidirectional"))
    )
    (net (code "38") (name "/EZFET_XT2OUT") (class "Default")
      (node (ref "Q101") (pin "3") (pinfunction "3_3") (pintype "passive"))
      (node (ref "U101") (pin "58") (pinfunction "P5.3/XT2OUT_58") (pintype "bidirectional"))
    )
    (net (code "39") (name "/HUB_DM2") (class "Default")
      (node (ref "R103") (pin "1") (pinfunction "1_1") (pintype "passive+no_connect"))
    )
    (net (code "40") (name "/HUB_DP2") (class "Default")
      (node (ref "R104") (pin "1") (pinfunction "1_1") (pintype "passive+no_connect"))
    )
    (net (code "41") (name "GND") (class "Default")
      (node (ref "C101") (pin "2") (pinfunction "2_2") (pintype "passive"))
      (node (ref "C102") (pin "2") (pinfunction "2_2") (pintype "passive"))
      (node (ref "C103") (pin "2") (pinfunction "2_2") (pintype "passive"))
      (node (ref "C104") (pin "2") (pinfunction "2_2") (pintype "passive"))
      (node (ref "C106") (pin "2") (pinfunction "-_2") (pintype "passive"))
      (node (ref "C107") (pin "2") (pinfunction "2_2") (pintype "passive"))
      (node (ref "C109") (pin "2") (pinfunction "-_2") (pintype "passive"))
      (node (ref "C110") (pin "2") (pinfunction "2_2") (pintype "passive"))
      (node (ref "C111") (pin "2") (pinfunction "2_2") (pintype "passive"))
      (node (ref "C112") (pin "2") (pinfunction "2_2") (pintype "passive"))
      (node (ref "C113") (pin "2") (pinfunction "2_2") (pintype "passive"))
      (node (ref "C115") (pin "2") (pinfunction "2_2") (pintype "passive"))
      (node (ref "C116") (pin "2") (pinfunction "2_2") (pintype "passive"))
      (node (ref "C117") (pin "2") (pinfunction "2_2") (pintype "passive"))
      (node (ref "C118") (pin "2") (pinfunction "2_2") (pintype "passive"))
      (node (ref "C119") (pin "2") (pinfunction "2_2") (pintype "passive"))
      (node (ref "C120") (pin "2") (pinfunction "2_2") (pintype "passive"))
      (node (ref "C121") (pin "2") (pinfunction "2_2") (pintype "passive"))
      (node (ref "C122") (pin "2") (pinfunction "2_2") (pintype "passive"))
      (node (ref "C123") (pin "2") (pinfunction "2_2") (pintype "passive"))
      (node (ref "C124") (pin "2") (pinfunction "2_2") (pintype "passive"))
      (node (ref "C125") (pin "2") (pinfunction "2_2") (pintype "passive"))
      (node (ref "D103") (pin "1") (pinfunction "A_1") (pintype "passive"))
      (node (ref "D103") (pin "2") (pinfunction "K_2") (pintype "passive"))
      (node (ref "LED101") (pin "2") (pinfunction "K_2") (pintype "passive"))
      (node (ref "LED102") (pin "2") (pinfunction "K_2") (pintype "passive"))
      (node (ref "Q101") (pin "2") (pinfunction "2_2") (pintype "passive"))
      (node (ref "R106") (pin "2") (pinfunction "2_2") (pintype "passive"))
      (node (ref "R107") (pin "1") (pinfunction "1_1") (pintype "passive"))
      (node (ref "R108") (pin "1") (pinfunction "1_1") (pintype "passive"))
      (node (ref "R113") (pin "1") (pinfunction "1_1") (pintype "passive"))
      (node (ref "R115") (pin "1") (pinfunction "1_1") (pintype "passive"))
      (node (ref "R119") (pin "2") (pinfunction "2_2") (pintype "passive"))
      (node (ref "R122") (pin "1") (pinfunction "1_1") (pintype "passive"))
      (node (ref "R125") (pin "1") (pinfunction "1_1") (pintype "passive"))
      (node (ref "TP8") (pin "1") (pintype "passive"))
      (node (ref "U101") (pin "14") (pinfunction "AVSS1_14") (pintype "power_in"))
      (node (ref "U101") (pin "16") (pinfunction "DVSS1_16") (pintype "power_in"))
      (node (ref "U101") (pin "39") (pinfunction "DVSS2_39") (pintype "power_in"))
      (node (ref "U101") (pin "49") (pinfunction "VSSU_49") (pintype "power_in"))
      (node (ref "U101") (pin "56") (pinfunction "AVSS2_56") (pintype "power_in"))
      (node (ref "U101") (pin "65") (pinfunction "QFN_PAD_65") (pintype "power_in"))
      (node (ref "U102") (pin "13") (pinfunction "AVSS_13") (pintype "power_in"))
      (node (ref "U102") (pin "14") (pinfunction "DVSS_14") (pintype "power_in"))
      (node (ref "U102") (pin "17") (pinfunction "QFN_PAD_17") (pintype "power_in"))
      (node (ref "U103") (pin "6") (pinfunction "GND_6") (pintype "power_in"))
    )
    (net (code "42") (name "Net-(D102-K)") (class "Default")
      (node (ref "D102") (pin "1") (pinfunction "A_1") (pintype "passive"))
      (node (ref "D102") (pin "2") (pinfunction "K_2") (pintype "passive"))
      (node (ref "R118") (pin "1") (pinfunction "1_1") (pintype "passive"))
      (node (ref "T102") (pin "1") (pinfunction "B_1") (pintype "passive"))
    )
    (net (code "43") (name "Net-(LED101-A)") (class "Default")
      (node (ref "LED101") (pin "1") (pinfunction "A_1") (pintype "passive"))
      (node (ref "R101") (pin "1") (pinfunction "1_1") (pintype "passive"))
    )
    (net (code "44") (name "Net-(LED102-A)") (class "Default")
      (node (ref "LED102") (pin "1") (pinfunction "A_1") (pintype "passive"))
      (node (ref "R102") (pin "1") (pinfunction "1_1") (pintype "passive"))
    )
    (net (code "45") (name "Net-(T101-D)") (class "Default")
      (node (ref "D103") (pin "3") (pinfunction "A_3") (pintype "passive"))
      (node (ref "L101") (pin "1") (pinfunction "1_1") (pintype "passive"))
      (node (ref "T101") (pin "3") (pinfunction "D_3") (pintype "passive"))
    )
    (net (code "46") (name "Net-(T101-G)") (class "Default")
      (node (ref "D102") (pin "3") (pinfunction "A_3") (pintype "passive"))
      (node (ref "R120") (pin "2") (pinfunction "2_2") (pintype "passive"))
      (node (ref "T101") (pin "1") (pinfunction "G_1") (pintype "passive"))
      (node (ref "T102") (pin "3") (pinfunction "C_3") (pintype "passive"))
    )
    (net (code "47") (name "Net-(T102-E)") (class "Default")
      (node (ref "R119") (pin "1") (pinfunction "1_1") (pintype "passive"))
      (node (ref "T102") (pin "2") (pinfunction "E_2") (pintype "passive"))
    )
    (net (code "48") (name "VCC_5V") (class "Default")
      (node (ref "C109") (pin "1") (pinfunction "+_1") (pintype "passive"))
      (node (ref "C117") (pin "1") (pinfunction "1_1") (pintype "passive"))
      (node (ref "C118") (pin "1") (pinfunction "1_1") (pintype "passive"))
      (node (ref "C125") (pin "1") (pinfunction "1_1") (pintype "passive"))
      (node (ref "R120") (pin "1") (pinfunction "1_1") (pintype "passive"))
      (node (ref "R124") (pin "2") (pinfunction "2_2") (pintype "passive"))
      (node (ref "T101") (pin "2") (pinfunction "S_2") (pintype "passive"))
      (node (ref "U101") (pin "53") (pinfunction "VBUS_53") (pintype "power_in"))
      (node (ref "U103") (pin "2") (pinfunction "V+_2") (pintype "power_in"))
    )
    (net (code "49") (name "VCC_LDO") (class "Default")
      (node (ref "C103") (pin "1") (pinfunction "1_1") (pintype "passive"))
      (node (ref "C104") (pin "1") (pinfunction "1_1") (pintype "passive"))
      (node (ref "C106") (pin "1") (pinfunction "+_1") (pintype "passive"))
      (node (ref "C113") (pin "1") (pinfunction "1_1") (pintype "passive"))
      (node (ref "C124") (pin "1") (pinfunction "1_1") (pintype "passive"))
      (node (ref "R109") (pin "2") (pinfunction "2_2") (pintype "passive"))
      (node (ref "R114") (pin "2") (pinfunction "2_2") (pintype "passive"))
      (node (ref "R116") (pin "2") (pinfunction "2_2") (pintype "passive"))
      (node (ref "R117") (pin "2") (pinfunction "2_2") (pintype "passive"))
      (node (ref "TP7") (pin "1") (pintype "passive"))
      (node (ref "U101") (pin "11") (pinfunction "AVCC1_11") (pintype "power_in"))
      (node (ref "U101") (pin "15") (pinfunction "DVCC1_15") (pintype "power_in"))
      (node (ref "U101") (pin "40") (pinfunction "DVCC2_40") (pintype "power_in"))
      (node (ref "U102") (pin "15") (pinfunction "AVCC_15") (pintype "power_in"))
      (node (ref "U102") (pin "16") (pinfunction "DVCC_16") (pintype "power_in"))
      (node (ref "U103") (pin "4") (pinfunction "COM2_4") (pintype "bidirectional"))
    )
    (net (code "50") (name "VCC_METERED") (class "Default")
      (node (ref "U103") (pin "1") (pinfunction "NO1_1") (pintype "bidirectional"))
      (node (ref "U103") (pin "5") (pinfunction "NO2_5") (pintype "bidirectional"))
    )
    (net (code "51") (name "unconnected-(U101-P1.0{slash}TA0CLK{slash}ACLK-Pad18)") (class "Default")
      (node (ref "U101") (pin "18") (pinfunction "P1.0/TA0CLK/ACLK_18") (pintype "bidirectional"))
    )
    (net (code "52") (name "unconnected-(U101-P1.1{slash}TA0.0-Pad19)") (class "Default")
      (node (ref "U101") (pin "19") (pinfunction "P1.1/TA0.0_19") (pintype "bidirectional"))
    )
    (net (code "53") (name "unconnected-(U101-P1.4{slash}TA0.3-Pad22)") (class "Default")
      (node (ref "U101") (pin "22") (pinfunction "P1.4/TA0.3_22") (pintype "bidirectional"))
    )
    (net (code "54") (name "unconnected-(U101-P1.5{slash}TA0.4-Pad23)") (class "Default")
      (node (ref "U101") (pin "23") (pinfunction "P1.5/TA0.4_23") (pintype "bidirectional"))
    )
    (net (code "55") (name "unconnected-(U101-P1.6{slash}TA1CLK{slash}CBOUT-Pad24)") (class "Default")
      (node (ref "U101") (pin "24") (pinfunction "P1.6/TA1CLK/CBOUT_24") (pintype "bidirectional"))
    )
    (net (code "56") (name "unconnected-(U101-P1.7{slash}TA1.0-Pad25)") (class "Default")
      (node (ref "U101") (pin "25") (pinfunction "P1.7/TA1.0_25") (pintype "bidirectional"))
    )
    (net (code "57") (name "unconnected-(U101-P2.3{slash}TA2.0-Pad29)") (class "Default")
      (node (ref "U101") (pin "29") (pinfunction "P2.3/TA2.0_29") (pintype "bidirectional"))
    )
    (net (code "58") (name "unconnected-(U101-P2.4{slash}TA2.1-Pad30)") (class "Default")
      (node (ref "U101") (pin "30") (pinfunction "P2.4/TA2.1_30") (pintype "bidirectional"))
    )
    (net (code "59") (name "unconnected-(U101-P2.5{slash}TA2.2-Pad31)") (class "Default")
      (node (ref "U101") (pin "31") (pinfunction "P2.5/TA2.2_31") (pintype "bidirectional"))
    )
    (net (code "60") (name "unconnected-(U101-P2.6{slash}RTCCLK{slash}DMAE0-Pad32)") (class "Default")
      (node (ref "U101") (pin "32") (pinfunction "P2.6/RTCCLK/DMAE0_32") (pintype "bidirectional"))
    )
    (net (code "61") (name "unconnected-(U101-P2.7{slash}UCB0STE{slash}UCA0CLK-Pad33)") (class "Default")
      (node (ref "U101") (pin "33") (pinfunction "P2.7/UCB0STE/UCA0CLK_33") (pintype "bidirectional"))
    )
    (net (code "62") (name "unconnected-(U101-P3.2{slash}UCB0CLK{slash}UCA0STE-Pad36)") (class "Default")
      (node (ref "U101") (pin "36") (pinfunction "P3.2/UCB0CLK/UCA0STE_36") (pintype "bidirectional"))
    )
    (net (code "63") (name "unconnected-(U101-P4.0{slash}PM_UCB1STE{slash}PM_UCA1CLK-Pad41)") (class "Default")
      (node (ref "U101") (pin "41") (pinfunction "P4.0/PM_UCB1STE/PM_UCA1CLK_41") (pintype "bidirectional"))
    )
    (net (code "64") (name "unconnected-(U101-P4.1{slash}PM_UCB1SIMO{slash}PM_UCB1SDA-Pad42)") (class "Default")
      (node (ref "U101") (pin "42") (pinfunction "P4.1/PM_UCB1SIMO/PM_UCB1SDA_42") (pintype "bidirectional"))
    )
    (net (code "65") (name "unconnected-(U101-P4.4{slash}PM_UCA1TXD{slash}PM_UCA1SIMO-Pad45)") (class "Default")
      (node (ref "U101") (pin "45") (pinfunction "P4.4/PM_UCA1TXD/PM_UCA1SIMO_45") (pintype "bidirectional"))
    )
    (net (code "66") (name "unconnected-(U101-P4.5{slash}PM_UCA1RXD{slash}PM_UCA1SOMI-Pad46)") (class "Default")
      (node (ref "U101") (pin "46") (pinfunction "P4.5/PM_UCA1RXD/PM_UCA1SOMI_46") (pintype "bidirectional"))
    )
    (net (code "67") (name "unconnected-(U101-P4.6{slash}PM_NONE-Pad47)") (class "Default")
      (node (ref "U101") (pin "47") (pinfunction "P4.6/PM_NONE_47") (pintype "bidirectional"))
    )
    (net (code "68") (name "unconnected-(U101-P4.7{slash}PM_NONE-Pad48)") (class "Default")
      (node (ref "U101") (pin "48") (pinfunction "P4.7/PM_NONE_48") (pintype "bidirectional"))
    )
    (net (code "69") (name "unconnected-(U101-P5.1{slash}A9{slash}VREF-{slash}VEREF--Pad10)") (class "Default")
      (node (ref "U101") (pin "10") (pinfunction "P5.1/A9/VREF-/VEREF-_10") (pintype "bidirectional"))
    )
    (net (code "70") (name "unconnected-(U101-P5.4{slash}XIN-Pad12)") (class "Default")
      (node (ref "U101") (pin "12") (pinfunction "P5.4/XIN_12") (pintype "bidirectional"))
    )
    (net (code "71") (name "unconnected-(U101-P5.5{slash}XOUT-Pad13)") (class "Default")
      (node (ref "U101") (pin "13") (pinfunction "P5.5/XOUT_13") (pintype "bidirectional"))
    )
    (net (code "72") (name "unconnected-(U101-P6.2{slash}CB2{slash}A2-Pad3)") (class "Default")
      (node (ref "U101") (pin "3") (pinfunction "P6.2/CB2/A2_3") (pintype "bidirectional"))
    )
    (net (code "73") (name "unconnected-(U101-P6.3{slash}CB3{slash}A3-Pad4)") (class "Default")
      (node (ref "U101") (pin "4") (pinfunction "P6.3/CB3/A3_4") (pintype "bidirectional"))
    )
  )
)
